# Schematic_Booster_GPS-EasyEDA.net
KiCad netlist of a schematic drawn in EasyEDA
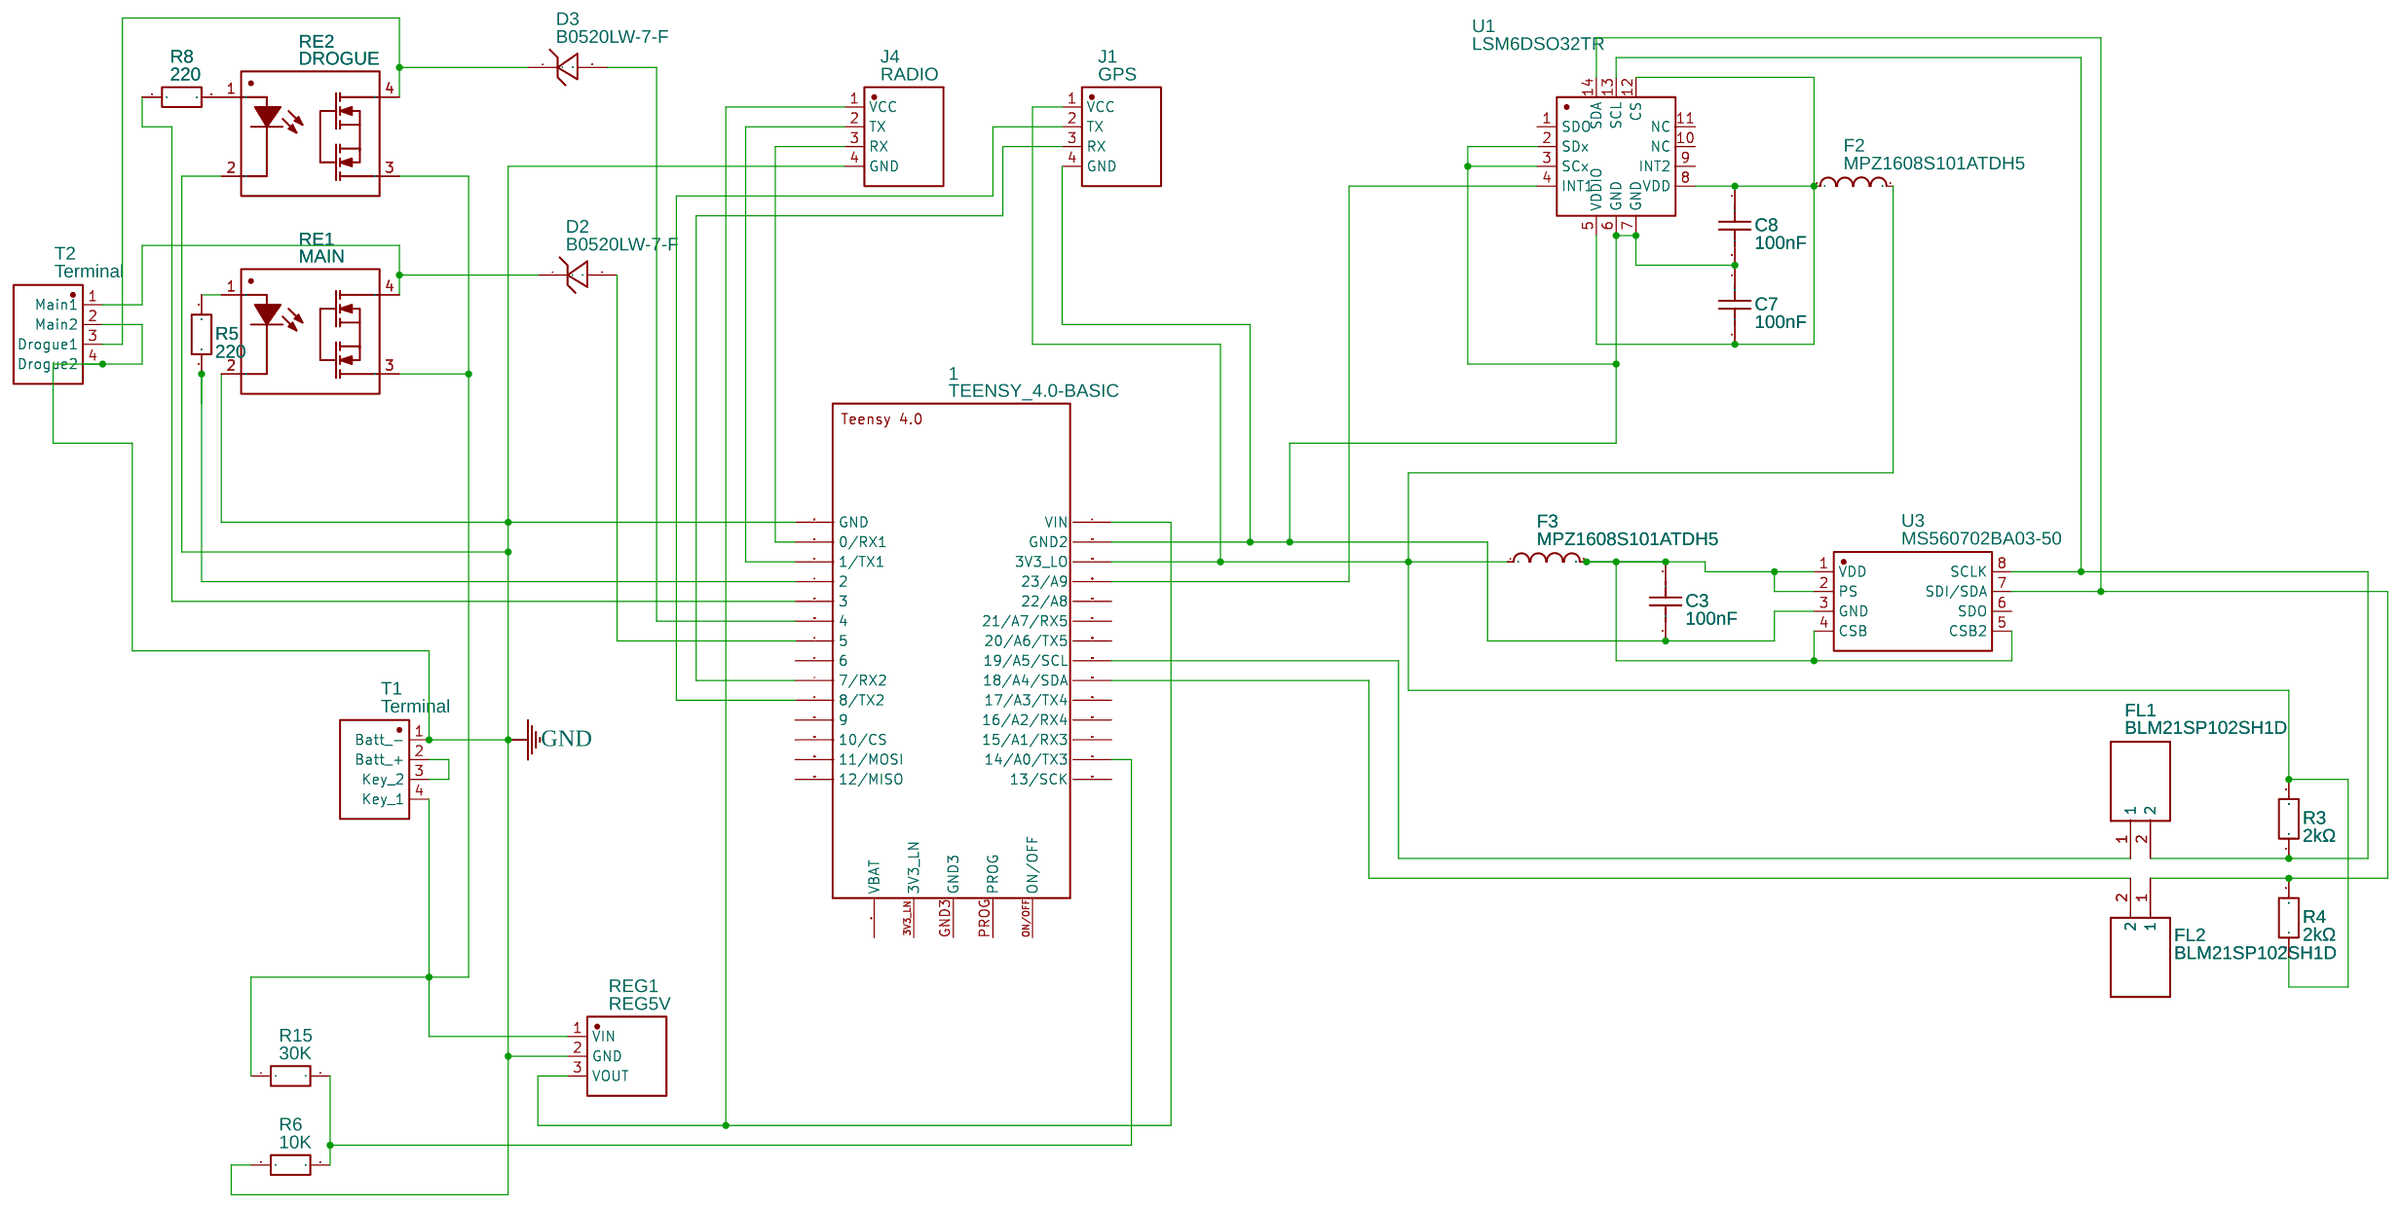
[diagram p0: schematic sheet]

(export (version "E")
  (design (tool "Eeschema 10.0.6"))
  (components
    (comp (ref "1") (value "TEENSY_4.0-BASIC") (libsource (lib "") (part "TEENSY_4.0-BASIC")))
    (comp (ref "C3")
      (value "100nF")
      (fields (field (name "Manufacturer Part") "CC0402KRX7R6BB104") (field (name "Manufacturer") "YAGEO"))
      (libsource (lib "") (part "CC0402KRX7R6BB104_1"))
    )
    (comp (ref "C7")
      (value "100nF")
      (fields (field (name "Manufacturer Part") "CC0402KRX7R6BB104") (field (name "Manufacturer") "YAGEO"))
      (libsource (lib "") (part "CC0402KRX7R6BB104"))
    )
    (comp (ref "C8")
      (value "100nF")
      (fields (field (name "Manufacturer Part") "CC0402KRX7R6BB104") (field (name "Manufacturer") "YAGEO"))
      (libsource (lib "") (part "CC0402KRX7R6BB104"))
    )
    (comp (ref "D2")
      (value "B0520LW-7-F")
      (fields (field (name "Manufacturer") "Diodes Incorporated"))
      (libsource (lib "") (part "B0520LW-7-F"))
    )
    (comp (ref "D3")
      (value "B0520LW-7-F")
      (fields (field (name "Manufacturer") "Diodes Incorporated"))
      (libsource (lib "") (part "B0520LW-7-F"))
    )
    (comp (ref "F2")
      (value "MPZ1608S101ATDH5")
      (fields (field (name "Manufacturer") "TDK"))
      (libsource (lib "") (part "MPZ1608S101ATDH5"))
    )
    (comp (ref "F3")
      (value "MPZ1608S101ATDH5")
      (fields (field (name "Manufacturer") "TDK"))
      (libsource (lib "") (part "MPZ1608S101ATDH5"))
    )
    (comp (ref "FL1") (value "BLM21SP102SH1D") (libsource (lib "") (part "BLM21SP102SH1D")))
    (comp (ref "FL2") (value "BLM21SP102SH1D") (libsource (lib "") (part "BLM21SP102SH1D_1")))
    (comp (ref "J1")
      (value "GPS")
      (fields
        (field (name "Manufacturer Part") "B4B-PH-K(LF)(SN)")
        (field (name "Manufacturer") "JST Sales America")
      )
      (libsource (lib "") (part "Unknown_565_-605"))
    )
    (comp (ref "J4")
      (value "RADIO")
      (fields
        (field (name "Manufacturer Part") "B4B-PH-K(LF)(SN)")
        (field (name "Manufacturer") "JST Sales America")
      )
      (libsource (lib "") (part "Unknown_455_-605"))
    )
    (comp (ref "R3")
      (value "2kΩ")
      (fields (field (name "Manufacturer Part") "ERA6AEB202V") (field (name "Manufacturer") "PANASONIC"))
      (libsource (lib "") (part "ERA6AEB202V"))
    )
    (comp (ref "R4")
      (value "2kΩ")
      (fields (field (name "Manufacturer Part") "ERA6AEB202V") (field (name "Manufacturer") "PANASONIC"))
      (libsource (lib "") (part "ERA6AEB202V"))
    )
    (comp (ref "R5")
      (value "220")
      (fields (field (name "Manufacturer Part") "ERJP06J221V") (field (name "Manufacturer") "PANASONIC"))
      (libsource (lib "") (part "ERJP06J221V"))
    )
    (comp (ref "R6")
      (value "10K")
      (fields (field (name "Manufacturer Part") "ERJP06J221V") (field (name "Manufacturer") "PANASONIC"))
      (libsource (lib "") (part "ERJP06J221V_1"))
    )
    (comp (ref "R8")
      (value "220")
      (fields (field (name "Manufacturer Part") "ERJP06J221V") (field (name "Manufacturer") "PANASONIC"))
      (libsource (lib "") (part "ERJP06J221V_1"))
    )
    (comp (ref "R15")
      (value "30K")
      (fields (field (name "Manufacturer Part") "ERJP06J221V") (field (name "Manufacturer") "PANASONIC"))
      (libsource (lib "") (part "ERJP06J221V_1"))
    )
    (comp (ref "RE1")
      (value "MAIN")
      (fields (field (name "Manufacturer Part") "AQY210EH") (field (name "Manufacturer") "PANASONIC"))
      (libsource (lib "") (part "AQY210EH"))
    )
    (comp (ref "RE2")
      (value "DROGUE")
      (fields (field (name "Manufacturer Part") "AQY210EH") (field (name "Manufacturer") "PANASONIC"))
      (libsource (lib "") (part "AQY210EH"))
    )
    (comp (ref "REG1") (value "REG5V") (libsource (lib "") (part "Unknown_325_-135")))
    (comp (ref "T1") (value "Terminal") (libsource (lib "") (part "Terminal4b")))
    (comp (ref "T2") (value "Terminal") (libsource (lib "") (part "Terminal4b_1")))
    (comp (ref "U1")
      (value "LSM6DSO32TR")
      (fields (field (name "Manufacturer") "STMicroelectronics"))
      (libsource (lib "") (part "LSM6DSO32TR"))
    )
    (comp (ref "U3")
      (value "MS560702BA03-50")
      (fields (field (name "Manufacturer") "TE Connectivity"))
      (libsource (lib "") (part "MS560702BA03-50"))
    )
  )
  (nets
    (net (code "1") (name "GND") (class "Default")
      (node (ref "1") (pin "GND") (pinfunction "GND_GND") (pintype "bidirectional"))
      (node (ref "J4") (pin "4") (pinfunction "GND_4") (pintype "unspecified"))
      (node (ref "R6") (pin "1") (pinfunction "1_1") (pintype "unspecified"))
      (node (ref "RE1") (pin "2") (pinfunction "K_2") (pintype "unspecified"))
      (node (ref "RE2") (pin "2") (pinfunction "K_2") (pintype "unspecified"))
      (node (ref "REG1") (pin "2") (pinfunction "GND_2") (pintype "unspecified"))
      (node (ref "T1") (pin "1") (pinfunction "Batt_-_1") (pintype "unspecified"))
      (node (ref "T2") (pin "2") (pinfunction "Main2_2") (pintype "unspecified"))
      (node (ref "T2") (pin "4") (pinfunction "Drogue2_4") (pintype "unspecified"))
    )
    (net (code "2") (name "Net-(1-0{slash}RX1)") (class "Default")
      (node (ref "1") (pin "0/RX") (pinfunction "0/RX1_0/RX") (pintype "bidirectional"))
      (node (ref "J4") (pin "3") (pinfunction "RX_3") (pintype "unspecified"))
    )
    (net (code "3") (name "Net-(1-1{slash}TX1)") (class "Default")
      (node (ref "1") (pin "1/TX") (pinfunction "1/TX1_1/TX") (pintype "bidirectional"))
      (node (ref "J4") (pin "2") (pinfunction "TX_2") (pintype "unspecified"))
    )
    (net (code "4") (name "Net-(1-3)") (class "Default")
      (node (ref "1") (pin "3/CANTX") (pinfunction "3_3/CANTX") (pintype "bidirectional"))
      (node (ref "R8") (pin "1") (pinfunction "1_1") (pintype "unspecified"))
    )
    (net (code "5") (name "Net-(1-4)") (class "Default")
      (node (ref "1") (pin "4/CANRX") (pinfunction "4_4/CANRX") (pintype "bidirectional"))
      (node (ref "D3") (pin "2") (pinfunction "2_2") (pintype "unspecified"))
    )
    (net (code "6") (name "Net-(1-7{slash}RX2)") (class "Default")
      (node (ref "1") (pin "7") (pinfunction "7/RX2_7") (pintype "bidirectional"))
      (node (ref "J1") (pin "3") (pinfunction "RX_3") (pintype "unspecified"))
    )
    (net (code "7") (name "Net-(1-8{slash}TX2)") (class "Default")
      (node (ref "1") (pin "8") (pinfunction "8/TX2_8") (pintype "bidirectional"))
      (node (ref "J1") (pin "2") (pinfunction "TX_2") (pintype "unspecified"))
    )
    (net (code "8") (name "Net-(1-14{slash}A0{slash}TX3)") (class "Default")
      (node (ref "1") (pin "14/A0") (pinfunction "14/A0/TX3_14/A0") (pintype "bidirectional"))
      (node (ref "R15") (pin "2") (pinfunction "2_2") (pintype "unspecified"))
      (node (ref "R6") (pin "2") (pinfunction "2_2") (pintype "unspecified"))
    )
    (net (code "9") (name "Net-(1-Pad2)") (class "Default")
      (node (ref "1") (pin "2") (pinfunction "2_2") (pintype "bidirectional"))
      (node (ref "R5") (pin "1") (pinfunction "1_1") (pintype "unspecified"))
    )
    (net (code "10") (name "Net-(1-Pad5)") (class "Default")
      (node (ref "1") (pin "5") (pinfunction "5_5") (pintype "bidirectional"))
      (node (ref "D2") (pin "2") (pinfunction "2_2") (pintype "unspecified"))
    )
    (net (code "11") (name "Net-(1-Pad18{slash}A4{slash}SDA)") (class "Default")
      (node (ref "1") (pin "18/A4/SDA") (pinfunction "18/A4/SDA_18/A4/SDA") (pintype "bidirectional"))
      (node (ref "FL2") (pin "2") (pinfunction "2_2") (pintype "bidirectional"))
    )
    (net (code "12") (name "Net-(1-Pad19{slash}A5{slash}SCL)") (class "Default")
      (node (ref "1") (pin "19/A5/SCL") (pinfunction "19/A5/SCL_19/A5/SCL") (pintype "bidirectional"))
      (node (ref "FL1") (pin "1") (pinfunction "1_1") (pintype "bidirectional"))
    )
    (net (code "13") (name "Net-(J1-GND)") (class "Default")
      (node (ref "1") (pin "GND2") (pinfunction "GND2_GND2") (pintype "bidirectional"))
      (node (ref "C3") (pin "1") (pinfunction "1_1") (pintype "unspecified"))
      (node (ref "C7") (pin "1") (pinfunction "1_1") (pintype "unspecified"))
      (node (ref "C8") (pin "2") (pinfunction "2_2") (pintype "unspecified"))
      (node (ref "J1") (pin "4") (pinfunction "GND_4") (pintype "unspecified"))
      (node (ref "U1") (pin "2") (pinfunction "SDx_2") (pintype "unspecified"))
      (node (ref "U1") (pin "3") (pinfunction "SCx_3") (pintype "unspecified"))
      (node (ref "U1") (pin "6") (pinfunction "GND_6") (pintype "unspecified"))
      (node (ref "U1") (pin "7") (pinfunction "GND_7") (pintype "unspecified"))
      (node (ref "U3") (pin "3") (pinfunction "GND_3") (pintype "unspecified"))
    )
    (net (code "14") (name "Net-(J1-VCC)") (class "Default")
      (node (ref "1") (pin "3V3_LO") (pinfunction "3V3_LO_3V3_LO") (pintype "bidirectional"))
      (node (ref "F2") (pin "2") (pinfunction "2_2") (pintype "unspecified"))
      (node (ref "F3") (pin "1") (pinfunction "1_1") (pintype "unspecified"))
      (node (ref "J1") (pin "1") (pinfunction "VCC_1") (pintype "unspecified"))
      (node (ref "R3") (pin "2") (pinfunction "2_2") (pintype "unspecified"))
      (node (ref "R4") (pin "1") (pinfunction "1_1") (pintype "unspecified"))
    )
    (net (code "15") (name "Net-(J4-VCC)") (class "Default")
      (node (ref "1") (pin "VIN") (pinfunction "VIN_VIN") (pintype "bidirectional"))
      (node (ref "J4") (pin "1") (pinfunction "VCC_1") (pintype "unspecified"))
      (node (ref "REG1") (pin "3") (pinfunction "VOUT_3") (pintype "unspecified"))
    )
    (net (code "16") (name "Net-(R5-Pad2)") (class "Default")
      (node (ref "R5") (pin "2") (pinfunction "2_2") (pintype "unspecified"))
      (node (ref "RE1") (pin "1") (pinfunction "1_1") (pintype "unspecified"))
    )
    (net (code "17") (name "Net-(R8-Pad2)") (class "Default")
      (node (ref "R8") (pin "2") (pinfunction "2_2") (pintype "unspecified"))
      (node (ref "RE2") (pin "1") (pinfunction "1_1") (pintype "unspecified"))
    )
    (net (code "18") (name "Net-(REG1-VIN)") (class "Default")
      (node (ref "R15") (pin "1") (pinfunction "1_1") (pintype "unspecified"))
      (node (ref "RE1") (pin "3") (pinfunction "3_3") (pintype "unspecified"))
      (node (ref "RE2") (pin "3") (pinfunction "3_3") (pintype "unspecified"))
      (node (ref "REG1") (pin "1") (pinfunction "VIN_1") (pintype "unspecified"))
      (node (ref "T1") (pin "4") (pinfunction "Key_1_4") (pintype "unspecified"))
    )
    (net (code "19") (name "Net-(T1-Batt_+)") (class "Default")
      (node (ref "T1") (pin "2") (pinfunction "Batt_+_2") (pintype "unspecified"))
      (node (ref "T1") (pin "3") (pinfunction "Key_2_3") (pintype "unspecified"))
    )
    (net (code "20") (name "Net-(T2-Drogue1)") (class "Default")
      (node (ref "D3") (pin "1") (pinfunction "1_1") (pintype "unspecified"))
      (node (ref "RE2") (pin "4") (pinfunction "4_4") (pintype "unspecified"))
      (node (ref "T2") (pin "3") (pinfunction "Drogue1_3") (pintype "unspecified"))
    )
    (net (code "21") (name "Net-(T2-Main1)") (class "Default")
      (node (ref "D2") (pin "1") (pinfunction "1_1") (pintype "unspecified"))
      (node (ref "RE1") (pin "4") (pinfunction "4_4") (pintype "unspecified"))
      (node (ref "T2") (pin "1") (pinfunction "Main1_1") (pintype "unspecified"))
    )
    (net (code "22") (name "Net-(U1-CS)") (class "Default")
      (node (ref "C7") (pin "2") (pinfunction "2_2") (pintype "unspecified"))
      (node (ref "C8") (pin "1") (pinfunction "1_1") (pintype "unspecified"))
      (node (ref "F2") (pin "1") (pinfunction "1_1") (pintype "unspecified"))
      (node (ref "U1") (pin "12") (pinfunction "CS_12") (pintype "unspecified"))
      (node (ref "U1") (pin "5") (pinfunction "VDDIO_5") (pintype "unspecified"))
      (node (ref "U1") (pin "8") (pinfunction "VDD_8") (pintype "unspecified"))
    )
    (net (code "23") (name "Net-(U1-INT1)") (class "Default")
      (node (ref "1") (pin "23/A9") (pinfunction "23/A9_23/A9") (pintype "bidirectional"))
      (node (ref "U1") (pin "4") (pinfunction "INT1_4") (pintype "unspecified"))
    )
    (net (code "24") (name "Net-(U1-SCL)") (class "Default")
      (node (ref "FL1") (pin "2") (pinfunction "2_2") (pintype "bidirectional"))
      (node (ref "R3") (pin "1") (pinfunction "1_1") (pintype "unspecified"))
      (node (ref "U1") (pin "13") (pinfunction "SCL_13") (pintype "unspecified"))
      (node (ref "U3") (pin "8") (pinfunction "SCLK_8") (pintype "unspecified"))
    )
    (net (code "25") (name "Net-(U1-SDA)") (class "Default")
      (node (ref "FL2") (pin "1") (pinfunction "1_1") (pintype "bidirectional"))
      (node (ref "R4") (pin "2") (pinfunction "2_2") (pintype "unspecified"))
      (node (ref "U1") (pin "14") (pinfunction "SDA_14") (pintype "unspecified"))
      (node (ref "U3") (pin "7") (pinfunction "SDI/SDA_7") (pintype "unspecified"))
    )
    (net (code "26") (name "Net-(U3-CSB)") (class "Default")
      (node (ref "C3") (pin "2") (pinfunction "2_2") (pintype "unspecified"))
      (node (ref "F3") (pin "2") (pinfunction "2_2") (pintype "unspecified"))
      (node (ref "U3") (pin "1") (pinfunction "VDD_1") (pintype "unspecified"))
      (node (ref "U3") (pin "2") (pinfunction "PS_2") (pintype "unspecified"))
      (node (ref "U3") (pin "4") (pinfunction "CSB_4") (pintype "unspecified"))
      (node (ref "U3") (pin "5") (pinfunction "CSB2_5") (pintype "unspecified"))
    )
    (net (code "27") (name "unconnected-(1-9-Pad9{slash}CS)") (class "Default")
      (node (ref "1") (pin "9/CS") (pinfunction "9_9/CS") (pintype "bidirectional"))
    )
    (net (code "28") (name "unconnected-(1-15{slash}A1{slash}RX3-Pad15{slash}A1)") (class "Default")
      (node (ref "1") (pin "15/A1") (pinfunction "15/A1/RX3_15/A1") (pintype "bidirectional"))
    )
    (net (code "29") (name "unconnected-(1-16{slash}A2{slash}RX4-Pad16{slash}A2)") (class "Default")
      (node (ref "1") (pin "16/A2") (pinfunction "16/A2/RX4_16/A2") (pintype "bidirectional"))
    )
    (net (code "30") (name "unconnected-(1-17{slash}A3{slash}TX4-Pad17{slash}A3)") (class "Default")
      (node (ref "1") (pin "17/A3") (pinfunction "17/A3/TX4_17/A3") (pintype "bidirectional"))
    )
    (net (code "31") (name "unconnected-(1-20{slash}A6{slash}TX5-Pad20{slash}A6)") (class "Default")
      (node (ref "1") (pin "20/A6") (pinfunction "20/A6/TX5_20/A6") (pintype "bidirectional"))
    )
    (net (code "32") (name "unconnected-(1-21{slash}A7{slash}RX5-Pad21{slash}A7)") (class "Default")
      (node (ref "1") (pin "21/A7") (pinfunction "21/A7/RX5_21/A7") (pintype "bidirectional"))
    )
    (net (code "33") (name "unconnected-(1-Pad3V3_LN)") (class "Default")
      (node (ref "1") (pin "3V3_LN") (pinfunction "3V3_LN_3V3_LN") (pintype "bidirectional"))
    )
    (net (code "34") (name "unconnected-(1-Pad6)") (class "Default")
      (node (ref "1") (pin "6") (pinfunction "6_6") (pintype "bidirectional"))
    )
    (net (code "35") (name "unconnected-(1-Pad10{slash}CS)") (class "Default")
      (node (ref "1") (pin "10/CS") (pinfunction "10/CS_10/CS") (pintype "bidirectional"))
    )
    (net (code "36") (name "unconnected-(1-Pad11{slash}MOSI)") (class "Default")
      (node (ref "1") (pin "11/MOSI") (pinfunction "11/MOSI_11/MOSI") (pintype "bidirectional"))
    )
    (net (code "37") (name "unconnected-(1-Pad12{slash}MISO)") (class "Default")
      (node (ref "1") (pin "12/MISO") (pinfunction "12/MISO_12/MISO") (pintype "bidirectional"))
    )
    (net (code "38") (name "unconnected-(1-Pad13{slash}SCK)") (class "Default")
      (node (ref "1") (pin "13/SCK") (pinfunction "13/SCK_13/SCK") (pintype "bidirectional"))
    )
    (net (code "39") (name "unconnected-(1-Pad22{slash}A8)") (class "Default")
      (node (ref "1") (pin "22/A8") (pinfunction "22/A8_22/A8") (pintype "bidirectional"))
    )
    (net (code "40") (name "unconnected-(1-PadGND3)") (class "Default")
      (node (ref "1") (pin "GND3") (pinfunction "GND3_GND3") (pintype "bidirectional"))
    )
    (net (code "41") (name "unconnected-(1-PadON{slash}OFF)") (class "Default")
      (node (ref "1") (pin "ON/OFF") (pinfunction "ON/OFF_ON/OFF") (pintype "bidirectional"))
    )
    (net (code "42") (name "unconnected-(1-PadPROG)") (class "Default")
      (node (ref "1") (pin "PROG") (pinfunction "PROG_PROG") (pintype "bidirectional"))
    )
    (net (code "43") (name "unconnected-(1-VBAT-PadVBAT\\)") (class "Default")
      (node (ref "1") (pin "VBAT\\") (pinfunction "VBAT_VBAT\\") (pintype "bidirectional"))
    )
    (net (code "44") (name "unconnected-(U1-INT2-Pad9)") (class "Default")
      (node (ref "U1") (pin "9") (pinfunction "INT2_9") (pintype "unspecified"))
    )
    (net (code "45") (name "unconnected-(U1-NC-Pad10)") (class "Default")
      (node (ref "U1") (pin "10") (pinfunction "NC_10") (pintype "unspecified"))
    )
    (net (code "46") (name "unconnected-(U1-NC-Pad11)") (class "Default")
      (node (ref "U1") (pin "11") (pinfunction "NC_11") (pintype "unspecified"))
    )
    (net (code "47") (name "unconnected-(U1-SDO-Pad1)") (class "Default")
      (node (ref "U1") (pin "1") (pinfunction "SDO_1") (pintype "unspecified"))
    )
    (net (code "48") (name "unconnected-(U3-SDO-Pad6)") (class "Default")
      (node (ref "U3") (pin "6") (pinfunction "SDO_6") (pintype "unspecified"))
    )
  )
)
